# Fake_Alarm.net
KiCad netlist of a schematic drawn in EAGLE
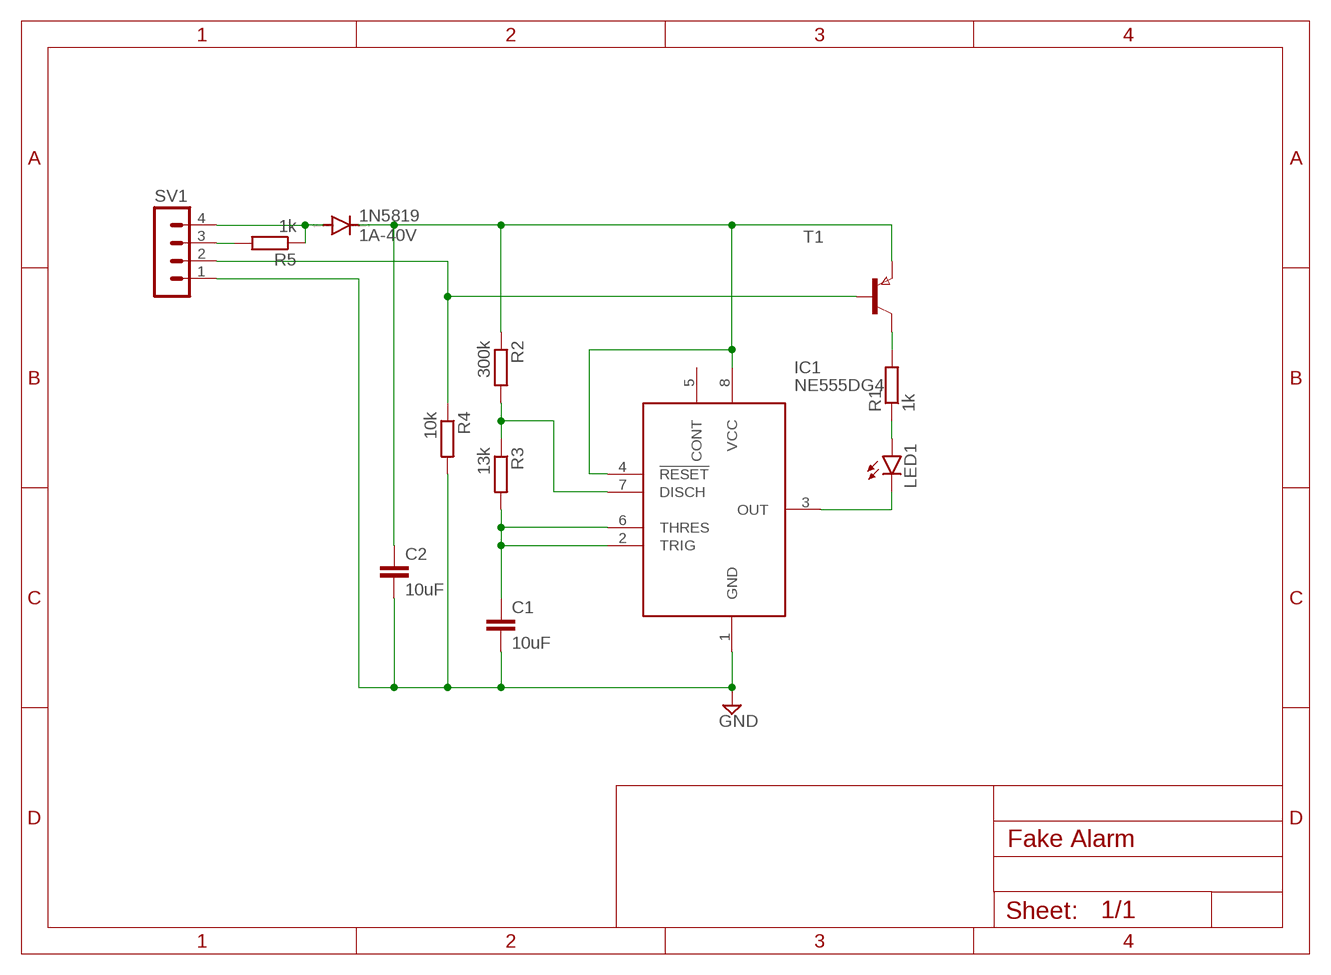
[diagram p0: schematic, sheet 1]

(export (version "E")
  (design (tool "Eeschema 10.0.6"))
  (components
    (comp (ref "1N5819")
      (value "1A-40V")
      (footprint "eagle-import:DO214AC")
      (libsource (lib "eagle-import") (part "DIODE-DO214AC"))
    )
    (comp (ref "C1")
      (value "10uF")
      (footprint "eagle-import:C0805K")
      (libsource (lib "eagle-import") (part "C-EUC0805K"))
    )
    (comp (ref "C2")
      (value "10uF")
      (footprint "eagle-import:C0805K")
      (libsource (lib "eagle-import") (part "C-EUC0805K"))
    )
    (comp (ref "IC1")
      (value "NE555DG4")
      (footprint "eagle-import:SOIC127P600X175-8N")
      (fields (field (name "MOUSER_PART_NUMBER") "595-NE555DG4"))
      (libsource (lib "eagle-import") (part "NE555DG4"))
    )
    (comp (ref "LED1")
      (value "LEDCHIP-LED0805")
      (footprint "eagle-import:CHIP-LED0805")
      (libsource (lib "eagle-import") (part "LEDCHIP-LED0805"))
    )
    (comp (ref "R1")
      (value "1k")
      (footprint "eagle-import:M0805")
      (libsource (lib "eagle-import") (part "R-EU_M0805"))
    )
    (comp (ref "R2")
      (value "300k")
      (footprint "eagle-import:M0805")
      (libsource (lib "eagle-import") (part "R-EU_M0805"))
    )
    (comp (ref "R3")
      (value "13k")
      (footprint "eagle-import:M0805")
      (libsource (lib "eagle-import") (part "R-EU_M0805"))
    )
    (comp (ref "R4")
      (value "10k")
      (footprint "eagle-import:M0805")
      (libsource (lib "eagle-import") (part "R-EU_M0805"))
    )
    (comp (ref "R5")
      (value "1k")
      (footprint "eagle-import:M0805")
      (libsource (lib "eagle-import") (part "R-EU_M0805"))
    )
    (comp (ref "SV1")
      (value "MA04-1")
      (footprint "eagle-import:MA04-1")
      (libsource (lib "eagle-import") (part "MA04-1"))
    )
    (comp (ref "T1")
      (value "PNPSOT23")
      (footprint "eagle-import:SOT-23")
      (fields (field (name "MPN") "DSS20200L-7"))
      (libsource (lib "eagle-import") (part "PNPSOT23"))
    )
  )
  (nets
    (net (code "1") (name "GND") (class "Default")
      (node (ref "C1") (pin "2") (pinfunction "2_2") (pintype "passive"))
      (node (ref "C2") (pin "2") (pinfunction "2_2") (pintype "passive"))
      (node (ref "IC1") (pin "1") (pinfunction "GND_1") (pintype "bidirectional"))
      (node (ref "R4") (pin "2") (pinfunction "2_2") (pintype "passive"))
      (node (ref "SV1") (pin "1") (pinfunction "1_1") (pintype "passive"))
    )
    (net (code "2") (name "Net-(1N5819-PadA)") (class "Default")
      (node (ref "1N5819") (pin "A") (pinfunction "A_A") (pintype "passive"))
      (node (ref "R5") (pin "1") (pinfunction "1_1") (pintype "passive"))
      (node (ref "SV1") (pin "4") (pinfunction "4_4") (pintype "passive"))
    )
    (net (code "3") (name "Net-(IC1-DISCH)") (class "Default")
      (node (ref "IC1") (pin "7") (pinfunction "DISCH_7") (pintype "bidirectional"))
      (node (ref "R2") (pin "2") (pinfunction "2_2") (pintype "passive"))
      (node (ref "R3") (pin "1") (pinfunction "1_1") (pintype "passive"))
    )
    (net (code "4") (name "Net-(IC1-OUT)") (class "Default")
      (node (ref "IC1") (pin "3") (pinfunction "OUT_3") (pintype "bidirectional"))
      (node (ref "LED1") (pin "C") (pinfunction "C_C") (pintype "passive"))
    )
    (net (code "5") (name "Net-(IC1-THRES)") (class "Default")
      (node (ref "C1") (pin "1") (pinfunction "1_1") (pintype "passive"))
      (node (ref "IC1") (pin "2") (pinfunction "TRIG_2") (pintype "bidirectional"))
      (node (ref "IC1") (pin "6") (pinfunction "THRES_6") (pintype "bidirectional"))
      (node (ref "R3") (pin "2") (pinfunction "2_2") (pintype "passive"))
    )
    (net (code "6") (name "Net-(IC1-VCC)") (class "Default")
      (node (ref "1N5819") (pin "C") (pinfunction "C_C") (pintype "passive"))
      (node (ref "C2") (pin "1") (pinfunction "1_1") (pintype "passive"))
      (node (ref "IC1") (pin "4") (pinfunction "~{RESET}_4") (pintype "bidirectional"))
      (node (ref "IC1") (pin "8") (pinfunction "VCC_8") (pintype "bidirectional"))
      (node (ref "R2") (pin "1") (pinfunction "1_1") (pintype "passive"))
      (node (ref "T1") (pin "2") (pinfunction "E_2") (pintype "passive"))
    )
    (net (code "7") (name "Net-(LED1-PadA)") (class "Default")
      (node (ref "LED1") (pin "A") (pinfunction "A_A") (pintype "passive"))
      (node (ref "R1") (pin "1") (pinfunction "1_1") (pintype "passive"))
    )
    (net (code "8") (name "Net-(R5-Pad2)") (class "Default")
      (node (ref "R5") (pin "2") (pinfunction "2_2") (pintype "passive"))
      (node (ref "SV1") (pin "3") (pinfunction "3_3") (pintype "passive"))
    )
    (net (code "9") (name "Net-(T1-B)") (class "Default")
      (node (ref "R4") (pin "1") (pinfunction "1_1") (pintype "passive"))
      (node (ref "SV1") (pin "2") (pinfunction "2_2") (pintype "passive"))
      (node (ref "T1") (pin "3") (pinfunction "B_3") (pintype "passive"))
    )
    (net (code "10") (name "Net-(T1-C)") (class "Default")
      (node (ref "R1") (pin "2") (pinfunction "2_2") (pintype "passive"))
      (node (ref "T1") (pin "1") (pinfunction "C_1") (pintype "passive"))
    )
    (net (code "11") (name "unconnected-(IC1-CONT-Pad5)") (class "Default")
      (node (ref "IC1") (pin "5") (pinfunction "CONT_5") (pintype "bidirectional"))
    )
  )
)
